# schematic.net
KiCad netlist of a schematic drawn in EasyEDA
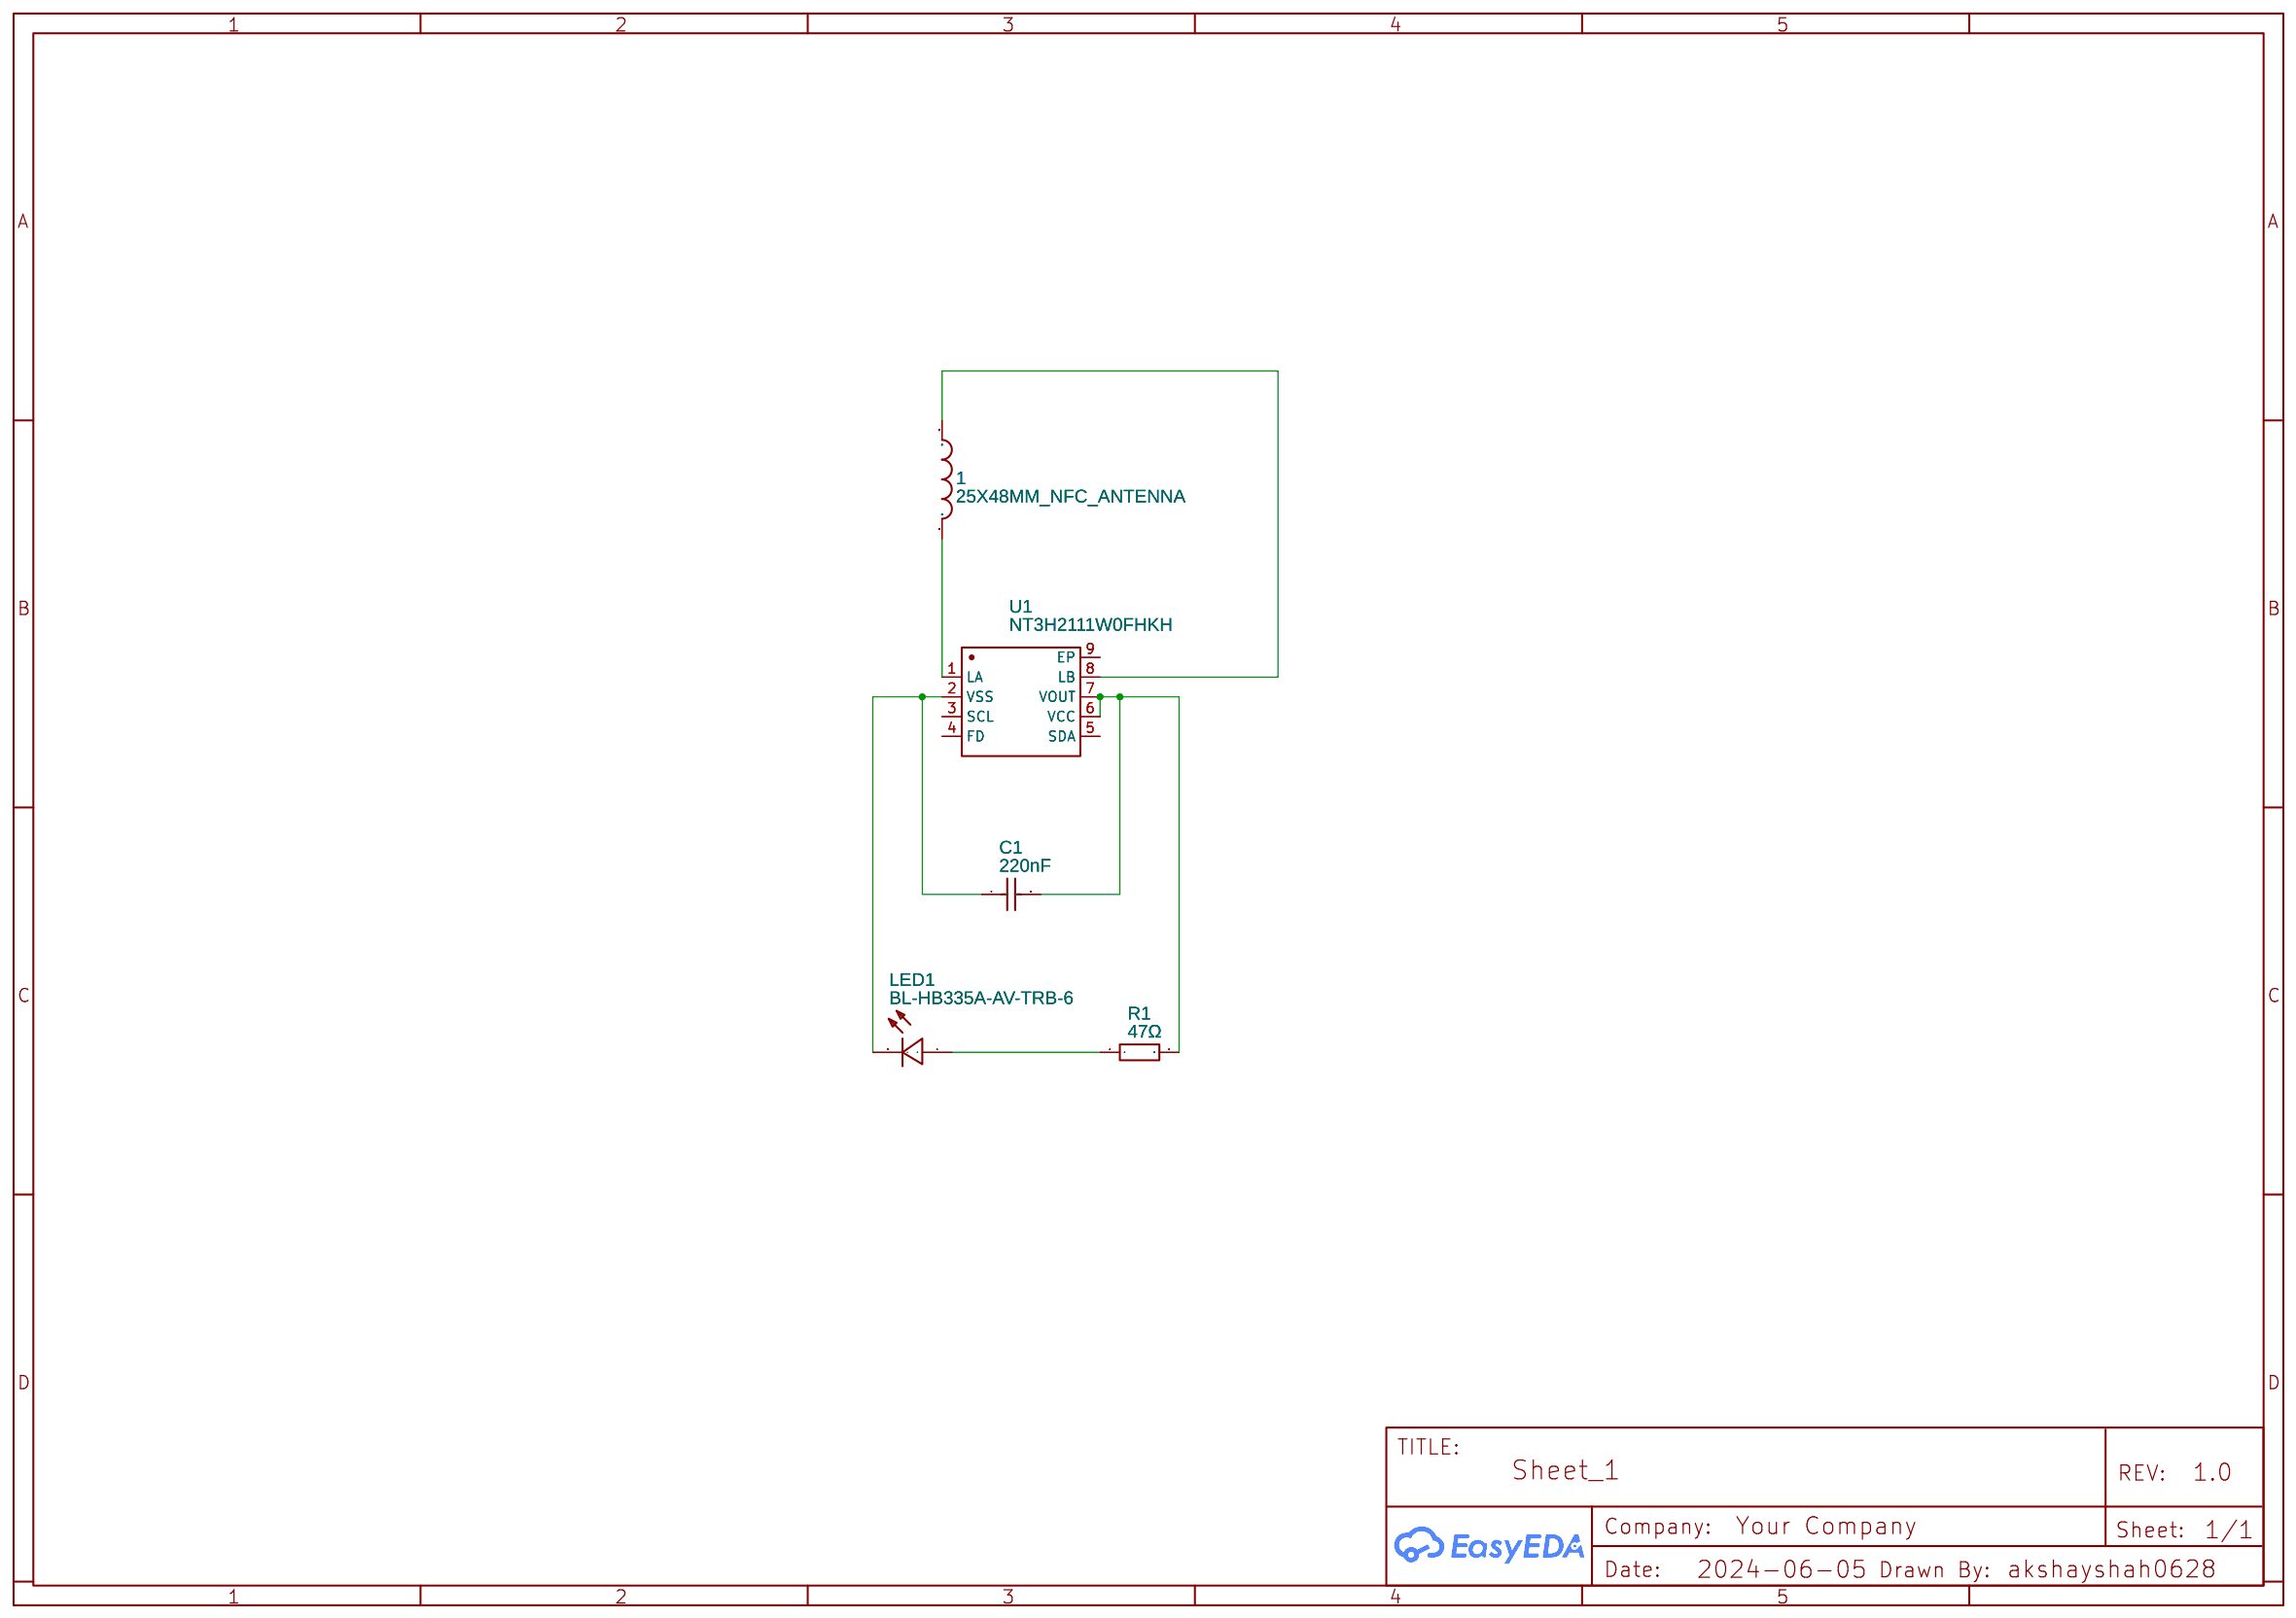
[diagram p0: schematic sheet]

(export (version "E")
  (design (tool "Eeschema 10.0.6"))
  (components
    (comp (ref "1") (value "25X48MM_NFC_ANTENNA") (libsource (lib "") (part "25X48MM_NFC_ANTENNA")))
    (comp (ref "C1")
      (value "220nF")
      (fields
        (field (name "Manufacturer Part") "CL10B224KA8NNNC")
        (field (name "Manufacturer") "SAMSUNG(三星)")
      )
      (libsource (lib "") (part "CL10B224KA8NNNC"))
    )
    (comp (ref "LED1")
      (value "BL-HB335A-AV-TRB-6")
      (fields (field (name "Manufacturer") "BrtLed(佰鸿)"))
      (libsource (lib "") (part "BL-HB335A-AV-TRB-6"))
    )
    (comp (ref "R1")
      (value "47Ω")
      (fields
        (field (name "Manufacturer Part") "0603WAF470JT5E")
        (field (name "Manufacturer") "UNI-ROYAL(厚声)")
      )
      (libsource (lib "") (part "0603WAF470JT5E"))
    )
    (comp (ref "U1")
      (value "NT3H2111W0FHKH")
      (fields (field (name "Manufacturer") "NXP(恩智浦)"))
      (libsource (lib "") (part "NT3H2111W0FHKH"))
    )
  )
  (nets
    (net (code "1") (name "Net-(LED1-+)") (class "Default")
      (node (ref "LED1") (pin "1") (pinfunction "+_1") (pintype "unspecified"))
      (node (ref "R1") (pin "1") (pinfunction "1_1") (pintype "input"))
    )
    (net (code "2") (name "Net-(LED1--)") (class "Default")
      (node (ref "C1") (pin "1") (pinfunction "1_1") (pintype "input"))
      (node (ref "LED1") (pin "2") (pinfunction "-_2") (pintype "unspecified"))
      (node (ref "U1") (pin "2") (pinfunction "VSS_2") (pintype "unspecified"))
    )
    (net (code "3") (name "Net-(U1-LA)") (class "Default")
      (node (ref "1") (pin "P$2") (pinfunction "P$2_P$2") (pintype "bidirectional"))
      (node (ref "U1") (pin "1") (pinfunction "LA_1") (pintype "unspecified"))
    )
    (net (code "4") (name "Net-(U1-LB)") (class "Default")
      (node (ref "1") (pin "P$1") (pinfunction "P$1_P$1") (pintype "bidirectional"))
      (node (ref "U1") (pin "8") (pinfunction "LB_8") (pintype "unspecified"))
    )
    (net (code "5") (name "Net-(U1-VCC)") (class "Default")
      (node (ref "C1") (pin "2") (pinfunction "2_2") (pintype "input"))
      (node (ref "R1") (pin "2") (pinfunction "2_2") (pintype "input"))
      (node (ref "U1") (pin "6") (pinfunction "VCC_6") (pintype "unspecified"))
      (node (ref "U1") (pin "7") (pinfunction "VOUT_7") (pintype "unspecified"))
    )
    (net (code "6") (name "unconnected-(U1-EP-Pad9)") (class "Default")
      (node (ref "U1") (pin "9") (pinfunction "EP_9") (pintype "unspecified"))
    )
    (net (code "7") (name "unconnected-(U1-FD-Pad4)") (class "Default")
      (node (ref "U1") (pin "4") (pinfunction "FD_4") (pintype "unspecified"))
    )
    (net (code "8") (name "unconnected-(U1-SCL-Pad3)") (class "Default")
      (node (ref "U1") (pin "3") (pinfunction "SCL_3") (pintype "unspecified"))
    )
    (net (code "9") (name "unconnected-(U1-SDA-Pad5)") (class "Default")
      (node (ref "U1") (pin "5") (pinfunction "SDA_5") (pintype "unspecified"))
    )
  )
)
